# LEPTON.net
KiCad netlist of a schematic drawn in EAGLE
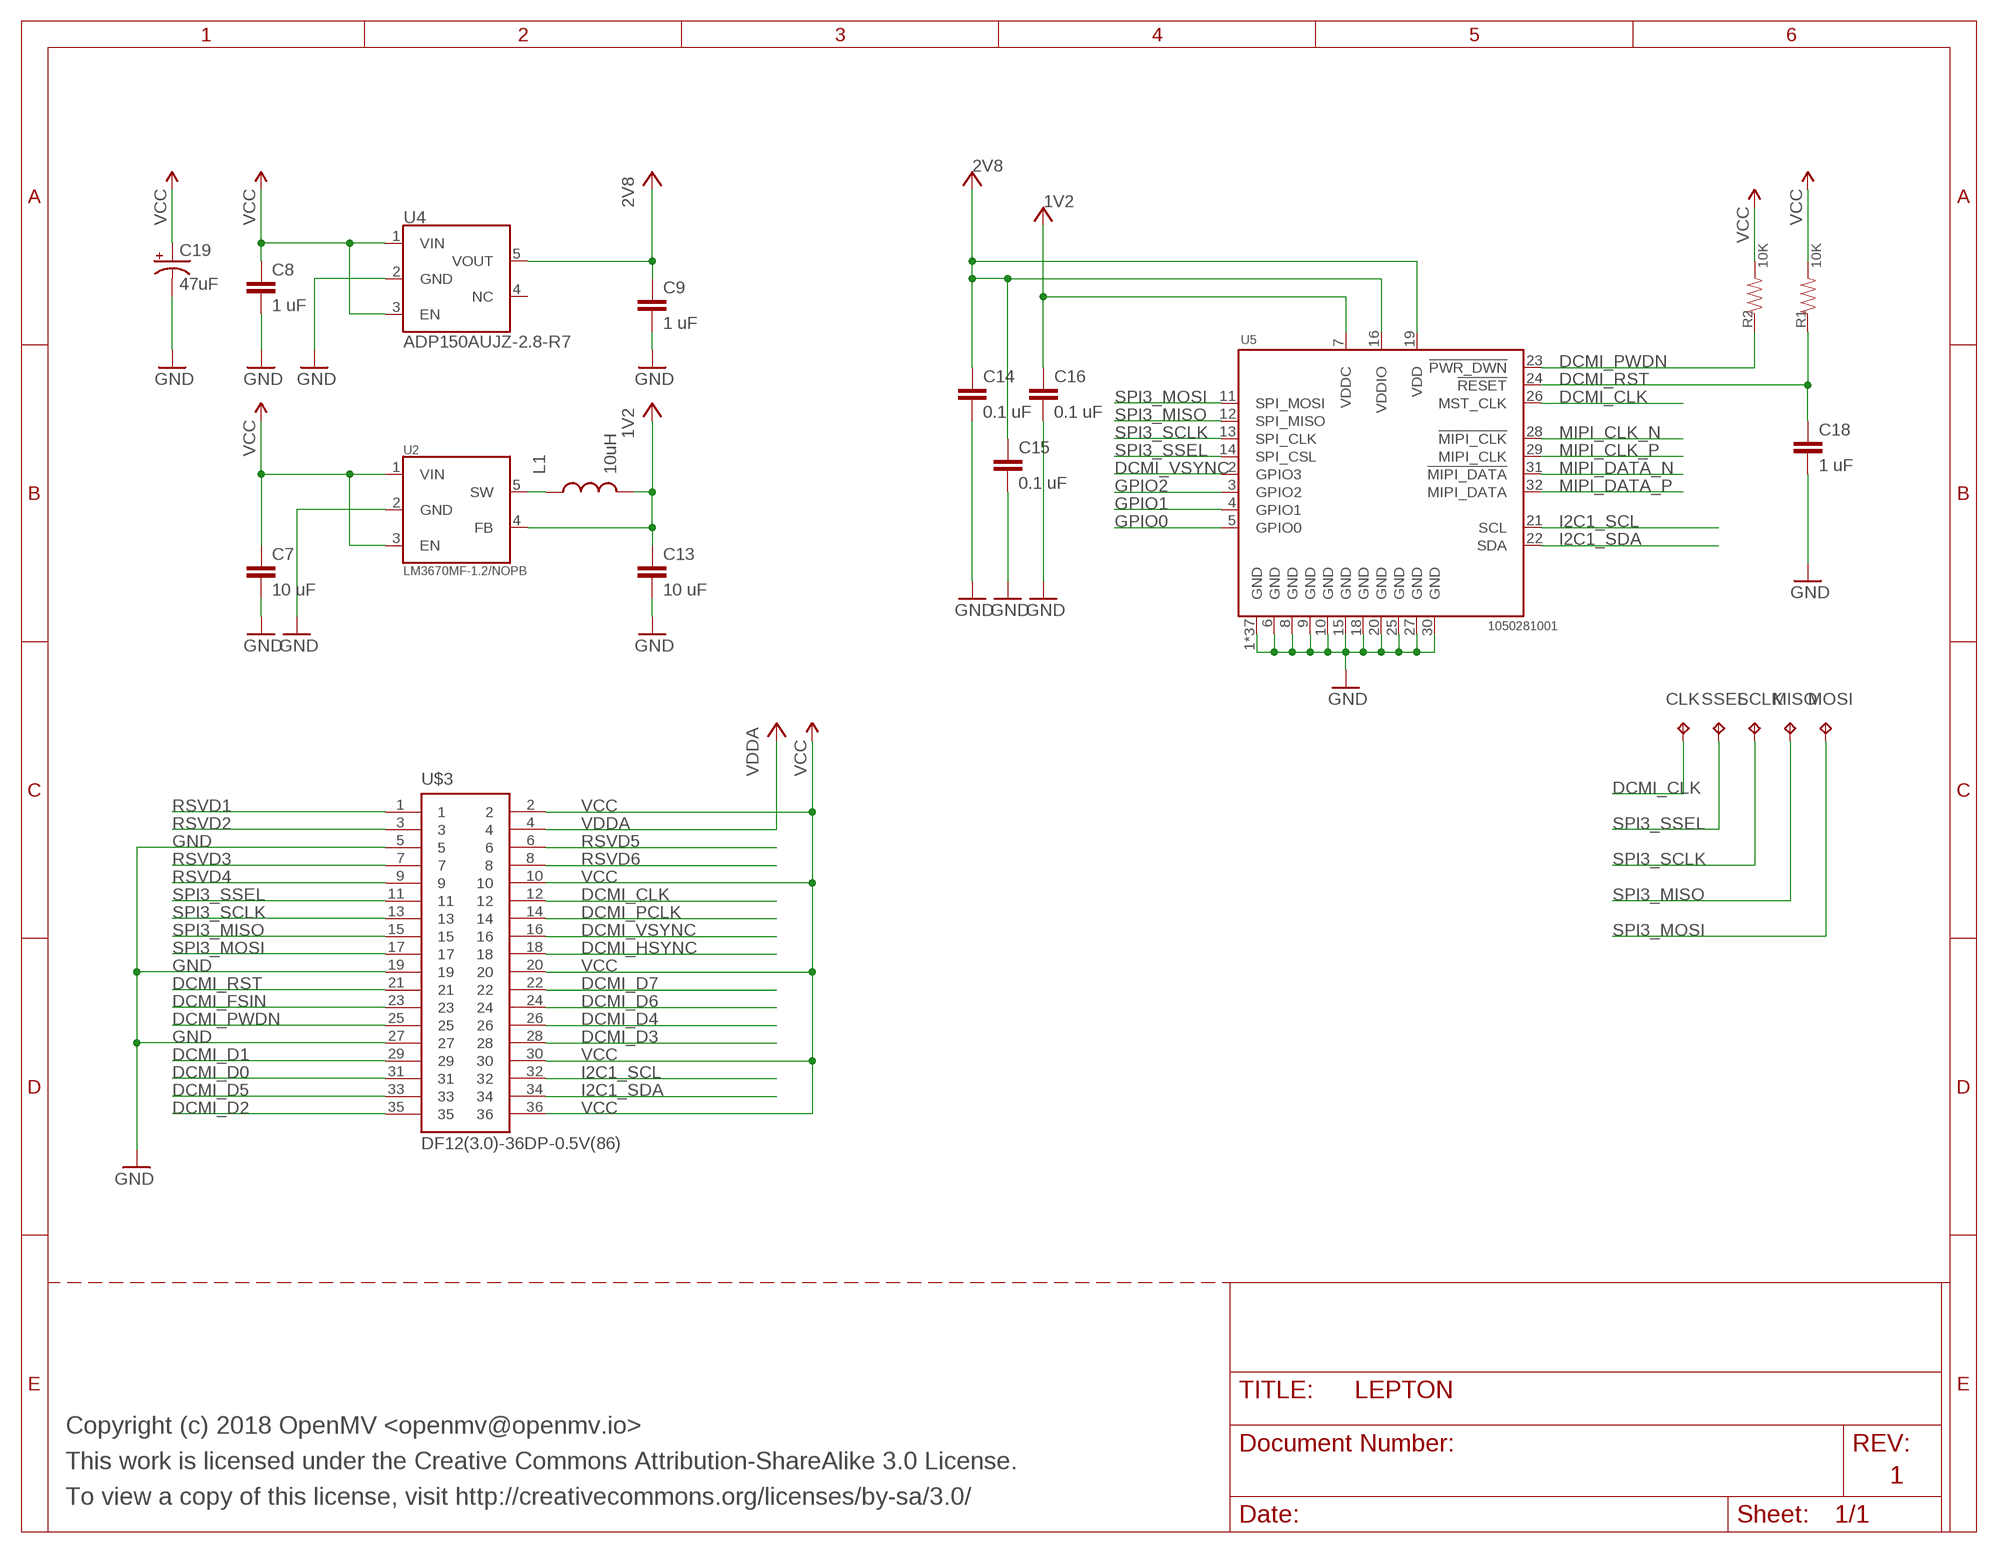
[diagram p0: schematic, sheet 1]

(export (version "E")
  (design (tool "Eeschema 10.0.6"))
  (components
    (comp (ref "C7")
      (value "10 uF")
      (footprint "eagle-import:0805")
      (libsource (lib "eagle-import") (part "CAP0805"))
    )
    (comp (ref "C8")
      (value "1 uF")
      (footprint "eagle-import:0402-CAP")
      (libsource (lib "eagle-import") (part "CAP0402-CAP"))
    )
    (comp (ref "C9")
      (value "1 uF")
      (footprint "eagle-import:0402-CAP")
      (libsource (lib "eagle-import") (part "CAP0402-CAP"))
    )
    (comp (ref "C13")
      (value "10 uF")
      (footprint "eagle-import:0805")
      (libsource (lib "eagle-import") (part "CAP0805"))
    )
    (comp (ref "C14")
      (value "0.1 uF")
      (footprint "eagle-import:0402-CAP")
      (libsource (lib "eagle-import") (part "CAP0402-CAP"))
    )
    (comp (ref "C15")
      (value "0.1 uF")
      (footprint "eagle-import:0402-CAP")
      (libsource (lib "eagle-import") (part "CAP0402-CAP"))
    )
    (comp (ref "C16")
      (value "0.1 uF")
      (footprint "eagle-import:0402-CAP")
      (libsource (lib "eagle-import") (part "CAP0402-CAP"))
    )
    (comp (ref "C18")
      (value "1 uF")
      (footprint "eagle-import:0402-CAP")
      (libsource (lib "eagle-import") (part "CAP0402-CAP"))
    )
    (comp (ref "C19")
      (value "47uF")
      (footprint "eagle-import:EIA3216")
      (libsource (lib "eagle-import") (part "CAP_POL1206"))
    )
    (comp (ref "CLK")
      (value "TPTP16R")
      (footprint "eagle-import:TP16R")
      (libsource (lib "eagle-import") (part "TPTP16R"))
    )
    (comp (ref "L1")
      (value "10uH")
      (footprint "eagle-import:1210")
      (libsource (lib "eagle-import") (part "INDUCTOR1210"))
    )
    (comp (ref "MISO")
      (value "TPTP16R")
      (footprint "eagle-import:TP16R")
      (libsource (lib "eagle-import") (part "TPTP16R"))
    )
    (comp (ref "MOSI")
      (value "TPTP16R")
      (footprint "eagle-import:TP16R")
      (libsource (lib "eagle-import") (part "TPTP16R"))
    )
    (comp (ref "R1")
      (value "10K")
      (footprint "eagle-import:0402-RES")
      (libsource (lib "eagle-import") (part "RESISTOR0402-RES"))
    )
    (comp (ref "R2")
      (value "10K")
      (footprint "eagle-import:0402-RES")
      (libsource (lib "eagle-import") (part "RESISTOR0402-RES"))
    )
    (comp (ref "SCLK")
      (value "TPTP16R")
      (footprint "eagle-import:TP16R")
      (libsource (lib "eagle-import") (part "TPTP16R"))
    )
    (comp (ref "SSEL")
      (value "TPTP16R")
      (footprint "eagle-import:TP16R")
      (libsource (lib "eagle-import") (part "TPTP16R"))
    )
    (comp (ref "U$3")
      (value "DF12(3.0)-36DP-0.5V(86)")
      (footprint "eagle-import:DF12-36-DP")
      (libsource (lib "eagle-import") (part "DF12-36-DP"))
    )
    (comp (ref "U2")
      (value "LM3670MF-1.2/NOPB")
      (footprint "eagle-import:SOT23-5")
      (libsource (lib "eagle-import") (part "LM3670SOT23-5"))
    )
    (comp (ref "U4")
      (value "ADP150AUJZ-2.8-R7")
      (footprint "eagle-import:SOT23-5")
      (libsource (lib "eagle-import") (part "ADP150TSOT-5"))
    )
    (comp (ref "U5")
      (value "1050281001")
      (footprint "eagle-import:CAM-SOCKET")
      (libsource (lib "eagle-import") (part "CAM-MODULE"))
    )
  )
  (nets
    (net (code "1") (name "/DCMI_CLK") (class "Default")
      (node (ref "CLK") (pin "TP") (pinfunction "TP_TP") (pintype "input"))
      (node (ref "U$3") (pin "12") (pinfunction "12_12") (pintype "bidirectional"))
      (node (ref "U5") (pin "26") (pinfunction "MST_CLK_26") (pintype "bidirectional"))
    )
    (net (code "2") (name "/DCMI_D0") (class "Default")
      (node (ref "U$3") (pin "31") (pinfunction "31_31") (pintype "bidirectional"))
    )
    (net (code "3") (name "/DCMI_D1") (class "Default")
      (node (ref "U$3") (pin "29") (pinfunction "29_29") (pintype "bidirectional"))
    )
    (net (code "4") (name "/DCMI_D2") (class "Default")
      (node (ref "U$3") (pin "35") (pinfunction "35_35") (pintype "bidirectional"))
    )
    (net (code "5") (name "/DCMI_D3") (class "Default")
      (node (ref "U$3") (pin "28") (pinfunction "28_28") (pintype "bidirectional"))
    )
    (net (code "6") (name "/DCMI_D4") (class "Default")
      (node (ref "U$3") (pin "26") (pinfunction "26_26") (pintype "bidirectional"))
    )
    (net (code "7") (name "/DCMI_D5") (class "Default")
      (node (ref "U$3") (pin "33") (pinfunction "33_33") (pintype "bidirectional"))
    )
    (net (code "8") (name "/DCMI_D6") (class "Default")
      (node (ref "U$3") (pin "24") (pinfunction "24_24") (pintype "bidirectional"))
    )
    (net (code "9") (name "/DCMI_D7") (class "Default")
      (node (ref "U$3") (pin "22") (pinfunction "22_22") (pintype "bidirectional"))
    )
    (net (code "10") (name "/DCMI_FSIN") (class "Default")
      (node (ref "U$3") (pin "23") (pinfunction "23_23") (pintype "bidirectional"))
    )
    (net (code "11") (name "/DCMI_HSYNC") (class "Default")
      (node (ref "U$3") (pin "18") (pinfunction "18_18") (pintype "bidirectional"))
    )
    (net (code "12") (name "/DCMI_PCLK") (class "Default")
      (node (ref "U$3") (pin "14") (pinfunction "14_14") (pintype "bidirectional"))
    )
    (net (code "13") (name "/DCMI_PWDN") (class "Default")
      (node (ref "R2") (pin "1") (pinfunction "1_1") (pintype "passive"))
      (node (ref "U$3") (pin "25") (pinfunction "25_25") (pintype "bidirectional"))
      (node (ref "U5") (pin "23") (pinfunction "~{PWR_DWN}_23") (pintype "bidirectional"))
    )
    (net (code "14") (name "/DCMI_RST") (class "Default")
      (node (ref "C18") (pin "1") (pinfunction "1_1") (pintype "passive"))
      (node (ref "R1") (pin "1") (pinfunction "1_1") (pintype "passive"))
      (node (ref "U$3") (pin "21") (pinfunction "21_21") (pintype "bidirectional"))
      (node (ref "U5") (pin "24") (pinfunction "~{RESET}_24") (pintype "bidirectional"))
    )
    (net (code "15") (name "/DCMI_VSYNC") (class "Default")
      (node (ref "U$3") (pin "16") (pinfunction "16_16") (pintype "bidirectional"))
      (node (ref "U5") (pin "2") (pinfunction "GPIO3_2") (pintype "bidirectional"))
    )
    (net (code "16") (name "/GPIO0") (class "Default")
      (node (ref "U5") (pin "5") (pinfunction "GPIO0_5") (pintype "bidirectional"))
    )
    (net (code "17") (name "/GPIO1") (class "Default")
      (node (ref "U5") (pin "4") (pinfunction "GPIO1_4") (pintype "bidirectional"))
    )
    (net (code "18") (name "/GPIO2") (class "Default")
      (node (ref "U5") (pin "3") (pinfunction "GPIO2_3") (pintype "bidirectional"))
    )
    (net (code "19") (name "/I2C1_SCL") (class "Default")
      (node (ref "U$3") (pin "32") (pinfunction "32_32") (pintype "bidirectional"))
      (node (ref "U5") (pin "21") (pinfunction "SCL_21") (pintype "bidirectional"))
    )
    (net (code "20") (name "/I2C1_SDA") (class "Default")
      (node (ref "U$3") (pin "34") (pinfunction "34_34") (pintype "bidirectional"))
      (node (ref "U5") (pin "22") (pinfunction "SDA_22") (pintype "bidirectional"))
    )
    (net (code "21") (name "/MIPI_CLK_N") (class "Default")
      (node (ref "U5") (pin "28") (pinfunction "~{MIPI_CLK}_28") (pintype "bidirectional"))
    )
    (net (code "22") (name "/MIPI_CLK_P") (class "Default")
      (node (ref "U5") (pin "29") (pinfunction "MIPI_CLK_29") (pintype "bidirectional"))
    )
    (net (code "23") (name "/MIPI_DATA_N") (class "Default")
      (node (ref "U5") (pin "31") (pinfunction "~{MIPI_DATA}_31") (pintype "bidirectional"))
    )
    (net (code "24") (name "/MIPI_DATA_P") (class "Default")
      (node (ref "U5") (pin "32") (pinfunction "MIPI_DATA_32") (pintype "bidirectional"))
    )
    (net (code "25") (name "/RSVD1") (class "Default")
      (node (ref "U$3") (pin "1") (pinfunction "1_1") (pintype "bidirectional"))
    )
    (net (code "26") (name "/RSVD2") (class "Default")
      (node (ref "U$3") (pin "3") (pinfunction "3_3") (pintype "bidirectional"))
    )
    (net (code "27") (name "/RSVD3") (class "Default")
      (node (ref "U$3") (pin "7") (pinfunction "7_7") (pintype "bidirectional"))
    )
    (net (code "28") (name "/RSVD4") (class "Default")
      (node (ref "U$3") (pin "9") (pinfunction "9_9") (pintype "bidirectional"))
    )
    (net (code "29") (name "/RSVD5") (class "Default")
      (node (ref "U$3") (pin "6") (pinfunction "6_6") (pintype "bidirectional"))
    )
    (net (code "30") (name "/RSVD6") (class "Default")
      (node (ref "U$3") (pin "8") (pinfunction "8_8") (pintype "bidirectional"))
    )
    (net (code "31") (name "/SPI3_MISO") (class "Default")
      (node (ref "MISO") (pin "TP") (pinfunction "TP_TP") (pintype "input"))
      (node (ref "U$3") (pin "15") (pinfunction "15_15") (pintype "bidirectional"))
      (node (ref "U5") (pin "12") (pinfunction "SPI_MISO_12") (pintype "bidirectional"))
    )
    (net (code "32") (name "/SPI3_MOSI") (class "Default")
      (node (ref "MOSI") (pin "TP") (pinfunction "TP_TP") (pintype "input"))
      (node (ref "U$3") (pin "17") (pinfunction "17_17") (pintype "bidirectional"))
      (node (ref "U5") (pin "11") (pinfunction "SPI_MOSI_11") (pintype "bidirectional"))
    )
    (net (code "33") (name "/SPI3_SCLK") (class "Default")
      (node (ref "SCLK") (pin "TP") (pinfunction "TP_TP") (pintype "input"))
      (node (ref "U$3") (pin "13") (pinfunction "13_13") (pintype "bidirectional"))
      (node (ref "U5") (pin "13") (pinfunction "SPI_CLK_13") (pintype "bidirectional"))
    )
    (net (code "34") (name "/SPI3_SSEL") (class "Default")
      (node (ref "SSEL") (pin "TP") (pinfunction "TP_TP") (pintype "input"))
      (node (ref "U$3") (pin "11") (pinfunction "11_11") (pintype "bidirectional"))
      (node (ref "U5") (pin "14") (pinfunction "SPI_CSL_14") (pintype "bidirectional"))
    )
    (net (code "35") (name "1V2") (class "Default")
      (node (ref "C13") (pin "1") (pinfunction "1_1") (pintype "passive"))
      (node (ref "C16") (pin "1") (pinfunction "1_1") (pintype "passive"))
      (node (ref "L1") (pin "2") (pinfunction "2_2") (pintype "passive"))
      (node (ref "U2") (pin "4") (pinfunction "FB_4") (pintype "bidirectional"))
      (node (ref "U5") (pin "7") (pinfunction "VDDC_7") (pintype "power_in"))
    )
    (net (code "36") (name "2V8") (class "Default")
      (node (ref "C14") (pin "1") (pinfunction "1_1") (pintype "passive"))
      (node (ref "C15") (pin "1") (pinfunction "1_1") (pintype "passive"))
      (node (ref "C9") (pin "1") (pinfunction "1_1") (pintype "passive"))
      (node (ref "U4") (pin "5") (pinfunction "VOUT_5") (pintype "power_in"))
      (node (ref "U5") (pin "16") (pinfunction "VDDIO_16") (pintype "power_in"))
      (node (ref "U5") (pin "19") (pinfunction "VDD_19") (pintype "power_in"))
    )
    (net (code "37") (name "GND") (class "Default")
      (node (ref "C13") (pin "2") (pinfunction "2_2") (pintype "passive"))
      (node (ref "C14") (pin "2") (pinfunction "2_2") (pintype "passive"))
      (node (ref "C15") (pin "2") (pinfunction "2_2") (pintype "passive"))
      (node (ref "C16") (pin "2") (pinfunction "2_2") (pintype "passive"))
      (node (ref "C18") (pin "2") (pinfunction "2_2") (pintype "passive"))
      (node (ref "C19") (pin "C") (pinfunction "-_C") (pintype "passive"))
      (node (ref "C7") (pin "2") (pinfunction "2_2") (pintype "passive"))
      (node (ref "C8") (pin "2") (pinfunction "2_2") (pintype "passive"))
      (node (ref "C9") (pin "2") (pinfunction "2_2") (pintype "passive"))
      (node (ref "U$3") (pin "19") (pinfunction "19_19") (pintype "bidirectional"))
      (node (ref "U$3") (pin "27") (pinfunction "27_27") (pintype "bidirectional"))
      (node (ref "U$3") (pin "5") (pinfunction "5_5") (pintype "bidirectional"))
      (node (ref "U2") (pin "2") (pinfunction "GND_2") (pintype "power_in"))
      (node (ref "U4") (pin "2") (pinfunction "GND_2") (pintype "power_in"))
      (node (ref "U5") (pin "1") (pinfunction "GND_1") (pintype "power_in"))
      (node (ref "U5") (pin "10") (pinfunction "GND_10") (pintype "power_in"))
      (node (ref "U5") (pin "15") (pinfunction "GND_15") (pintype "power_in"))
      (node (ref "U5") (pin "18") (pinfunction "GND_18") (pintype "power_in"))
      (node (ref "U5") (pin "20") (pinfunction "GND_20") (pintype "power_in"))
      (node (ref "U5") (pin "25") (pinfunction "GND_25") (pintype "power_in"))
      (node (ref "U5") (pin "27") (pinfunction "GND_27") (pintype "power_in"))
      (node (ref "U5") (pin "30") (pinfunction "GND_30") (pintype "power_in"))
      (node (ref "U5") (pin "6") (pinfunction "GND_6") (pintype "power_in"))
      (node (ref "U5") (pin "8") (pinfunction "GND_8") (pintype "power_in"))
      (node (ref "U5") (pin "9") (pinfunction "GND_9") (pintype "power_in"))
      (node (ref "U5") (pin "P$1") (pinfunction "GND_P$1") (pintype "power_in"))
      (node (ref "U5") (pin "P$10") (pinfunction "GND_P$10") (pintype "power_in"))
      (node (ref "U5") (pin "P$11") (pinfunction "GND_P$11") (pintype "power_in"))
      (node (ref "U5") (pin "P$12") (pinfunction "GND_P$12") (pintype "power_in"))
      (node (ref "U5") (pin "P$13") (pinfunction "GND_P$13") (pintype "power_in"))
      (node (ref "U5") (pin "P$14") (pinfunction "GND_P$14") (pintype "power_in"))
      (node (ref "U5") (pin "P$15") (pinfunction "GND_P$15") (pintype "power_in"))
      (node (ref "U5") (pin "P$16") (pinfunction "GND_P$16") (pintype "power_in"))
      (node (ref "U5") (pin "P$17") (pinfunction "GND_P$17") (pintype "power_in"))
      (node (ref "U5") (pin "P$18") (pinfunction "GND_P$18") (pintype "power_in"))
      (node (ref "U5") (pin "P$19") (pinfunction "GND_P$19") (pintype "power_in"))
      (node (ref "U5") (pin "P$2") (pinfunction "GND_P$2") (pintype "power_in"))
      (node (ref "U5") (pin "P$20") (pinfunction "GND_P$20") (pintype "power_in"))
      (node (ref "U5") (pin "P$21") (pinfunction "GND_P$21") (pintype "power_in"))
      (node (ref "U5") (pin "P$22") (pinfunction "GND_P$22") (pintype "power_in"))
      (node (ref "U5") (pin "P$23") (pinfunction "GND_P$23") (pintype "power_in"))
      (node (ref "U5") (pin "P$24") (pinfunction "GND_P$24") (pintype "power_in"))
      (node (ref "U5") (pin "P$25") (pinfunction "GND_P$25") (pintype "power_in"))
      (node (ref "U5") (pin "P$26") (pinfunction "GND_P$26") (pintype "power_in"))
      (node (ref "U5") (pin "P$27") (pinfunction "GND_P$27") (pintype "power_in"))
      (node (ref "U5") (pin "P$28") (pinfunction "GND_P$28") (pintype "power_in"))
      (node (ref "U5") (pin "P$29") (pinfunction "GND_P$29") (pintype "power_in"))
      (node (ref "U5") (pin "P$3") (pinfunction "GND_P$3") (pintype "power_in"))
      (node (ref "U5") (pin "P$30") (pinfunction "GND_P$30") (pintype "power_in"))
      (node (ref "U5") (pin "P$31") (pinfunction "GND_P$31") (pintype "power_in"))
      (node (ref "U5") (pin "P$32") (pinfunction "GND_P$32") (pintype "power_in"))
      (node (ref "U5") (pin "P$33") (pinfunction "GND_P$33") (pintype "power_in"))
      (node (ref "U5") (pin "P$34") (pinfunction "GND_P$34") (pintype "power_in"))
      (node (ref "U5") (pin "P$35") (pinfunction "GND_P$35") (pintype "power_in"))
      (node (ref "U5") (pin "P$36") (pinfunction "GND_P$36") (pintype "power_in"))
      (node (ref "U5") (pin "P$4") (pinfunction "GND_P$4") (pintype "power_in"))
      (node (ref "U5") (pin "P$5") (pinfunction "GND_P$5") (pintype "power_in"))
      (node (ref "U5") (pin "P$6") (pinfunction "GND_P$6") (pintype "power_in"))
      (node (ref "U5") (pin "P$7") (pinfunction "GND_P$7") (pintype "power_in"))
      (node (ref "U5") (pin "P$8") (pinfunction "GND_P$8") (pintype "power_in"))
      (node (ref "U5") (pin "P$9") (pinfunction "GND_P$9") (pintype "power_in"))
    )
    (net (code "38") (name "Net-(U2-SW)") (class "Default")
      (node (ref "L1") (pin "1") (pinfunction "1_1") (pintype "passive"))
      (node (ref "U2") (pin "5") (pinfunction "SW_5") (pintype "power_in"))
    )
    (net (code "39") (name "VCC") (class "Default")
      (node (ref "C19") (pin "A") (pinfunction "+_A") (pintype "passive"))
      (node (ref "C7") (pin "1") (pinfunction "1_1") (pintype "passive"))
      (node (ref "C8") (pin "1") (pinfunction "1_1") (pintype "passive"))
      (node (ref "R1") (pin "2") (pinfunction "2_2") (pintype "passive"))
      (node (ref "R2") (pin "2") (pinfunction "2_2") (pintype "passive"))
      (node (ref "U$3") (pin "10") (pinfunction "10_10") (pintype "bidirectional"))
      (node (ref "U$3") (pin "2") (pinfunction "2_2") (pintype "bidirectional"))
      (node (ref "U$3") (pin "20") (pinfunction "20_20") (pintype "bidirectional"))
      (node (ref "U$3") (pin "30") (pinfunction "30_30") (pintype "bidirectional"))
      (node (ref "U$3") (pin "36") (pinfunction "36_36") (pintype "bidirectional"))
      (node (ref "U2") (pin "1") (pinfunction "VIN_1") (pintype "power_in"))
      (node (ref "U2") (pin "3") (pinfunction "EN_3") (pintype "bidirectional"))
      (node (ref "U4") (pin "1") (pinfunction "VIN_1") (pintype "power_in"))
      (node (ref "U4") (pin "3") (pinfunction "EN_3") (pintype "bidirectional"))
    )
    (net (code "40") (name "VDDA") (class "Default")
      (node (ref "U$3") (pin "4") (pinfunction "4_4") (pintype "bidirectional"))
    )
    (net (code "41") (name "unconnected-(U4-NC-Pad4)") (class "Default")
      (node (ref "U4") (pin "4") (pinfunction "NC_4") (pintype "bidirectional"))
    )
  )
)
